# shitty_dispenser_B.net
KiCad netlist of a schematic drawn in EAGLE
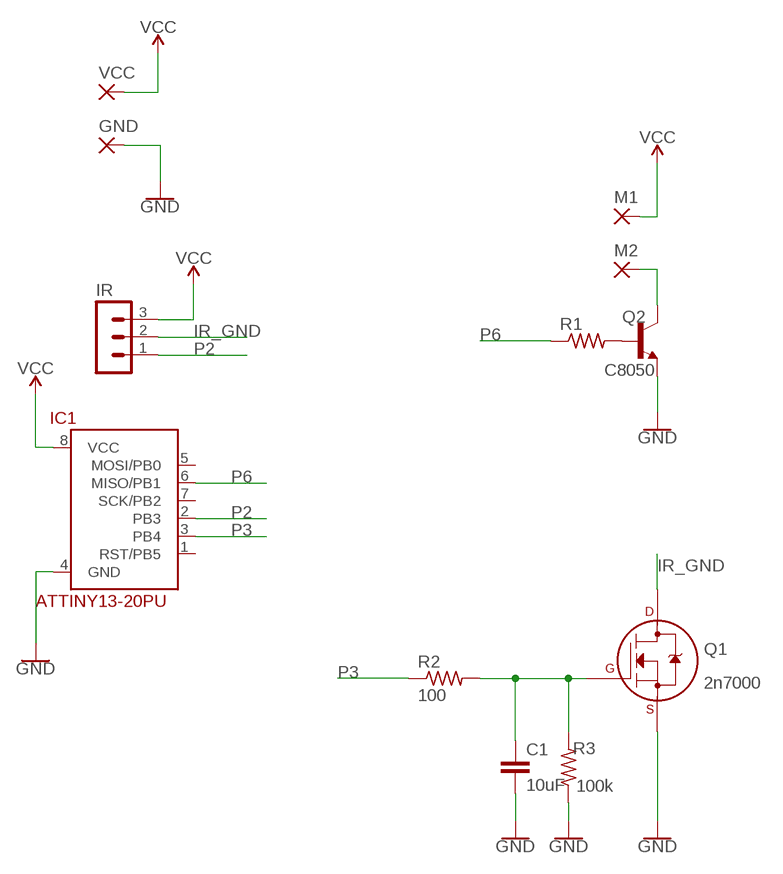
[diagram p0: schematic, sheet 1]

(export (version "E")
  (design (tool "Eeschema 10.0.6"))
  (components
    (comp (ref "C1")
      (value "10uF")
      (footprint "eagle-import:C025-025X050")
      (libsource (lib "eagle-import") (part "C-EU025-025X050"))
    )
    (comp (ref "GND")
      (value "2,54/1,0")
      (footprint "eagle-import:2,54_1,0")
      (libsource (lib "eagle-import") (part "wirepad_412_2,54/1,0"))
    )
    (comp (ref "IC1")
      (value "ATTINY13-20PU")
      (footprint "eagle-import:DIL08")
      (libsource (lib "eagle-import") (part "ATTINY13-20PU"))
    )
    (comp (ref "IR")
      (value "MA03-1")
      (footprint "eagle-import:MA03-1")
      (libsource (lib "eagle-import") (part "MA03-1"))
    )
    (comp (ref "M1")
      (value "2,54/1,0")
      (footprint "eagle-import:2,54_1,0")
      (libsource (lib "eagle-import") (part "2,54/1,0"))
    )
    (comp (ref "M2")
      (value "2,54/1,0")
      (footprint "eagle-import:2,54_1,0")
      (libsource (lib "eagle-import") (part "2,54/1,0"))
    )
    (comp (ref "Q1")
      (value "2n7000")
      (footprint "eagle-import:TO92-")
      (libsource (lib "eagle-import") (part "2N700_TO92-"))
    )
    (comp (ref "Q2")
      (value "C8050")
      (footprint "eagle-import:TO92-EBC")
      (libsource (lib "eagle-import") (part "-NPN-TO92-EBC29"))
    )
    (comp (ref "R1")
      (value "R-US_0204/7")
      (footprint "eagle-import:0204_7")
      (libsource (lib "eagle-import") (part "R-US_0204/7"))
    )
    (comp (ref "R2")
      (value "100")
      (footprint "eagle-import:0204_7")
      (libsource (lib "eagle-import") (part "R-US_0204/7"))
    )
    (comp (ref "R3")
      (value "100k")
      (footprint "eagle-import:0204_7")
      (libsource (lib "eagle-import") (part "R-US_0204/7"))
    )
    (comp (ref "VCC")
      (value "2,54/1,0")
      (footprint "eagle-import:2,54_1,0")
      (libsource (lib "eagle-import") (part "wirepad_412_2,54/1,0"))
    )
  )
  (nets
    (net (code "1") (name "/IR_GND") (class "Default")
      (node (ref "IR") (pin "2") (pinfunction "2_2") (pintype "passive"))
      (node (ref "Q1") (pin "1") (pinfunction "D_1") (pintype "bidirectional"))
    )
    (net (code "2") (name "/P2") (class "Default")
      (node (ref "IC1") (pin "2") (pinfunction "PB3_2") (pintype "bidirectional"))
      (node (ref "IR") (pin "1") (pinfunction "1_1") (pintype "passive"))
    )
    (net (code "3") (name "/P3") (class "Default")
      (node (ref "IC1") (pin "3") (pinfunction "PB4_3") (pintype "bidirectional"))
      (node (ref "R2") (pin "1") (pinfunction "1_1") (pintype "passive"))
    )
    (net (code "4") (name "/P6") (class "Default")
      (node (ref "IC1") (pin "6") (pinfunction "MISO/PB1_6") (pintype "bidirectional"))
      (node (ref "R1") (pin "1") (pinfunction "1_1") (pintype "passive"))
    )
    (net (code "5") (name "GND") (class "Default")
      (node (ref "C1") (pin "2") (pinfunction "2_2") (pintype "passive"))
      (node (ref "GND") (pin "1") (pinfunction "P_1") (pintype "passive"))
      (node (ref "IC1") (pin "4") (pinfunction "GND_4") (pintype "power_in"))
      (node (ref "Q1") (pin "3") (pinfunction "S_3") (pintype "bidirectional"))
      (node (ref "Q2") (pin "E") (pinfunction "E_E") (pintype "passive"))
      (node (ref "R3") (pin "1") (pinfunction "1_1") (pintype "passive"))
    )
    (net (code "6") (name "Net-(M2-P)") (class "Default")
      (node (ref "M2") (pin "1") (pinfunction "P_1") (pintype "passive"))
      (node (ref "Q2") (pin "C") (pinfunction "C_C") (pintype "passive"))
    )
    (net (code "7") (name "Net-(Q1-G)") (class "Default")
      (node (ref "C1") (pin "1") (pinfunction "1_1") (pintype "passive"))
      (node (ref "Q1") (pin "2") (pinfunction "G_2") (pintype "tri_state"))
      (node (ref "R2") (pin "2") (pinfunction "2_2") (pintype "passive"))
      (node (ref "R3") (pin "2") (pinfunction "2_2") (pintype "passive"))
    )
    (net (code "8") (name "Net-(Q2-PadB)") (class "Default")
      (node (ref "Q2") (pin "B") (pinfunction "B_B") (pintype "passive"))
      (node (ref "R1") (pin "2") (pinfunction "2_2") (pintype "passive"))
    )
    (net (code "9") (name "VCC") (class "Default")
      (node (ref "IC1") (pin "8") (pinfunction "VCC_8") (pintype "power_in"))
      (node (ref "IR") (pin "3") (pinfunction "3_3") (pintype "passive"))
      (node (ref "M1") (pin "1") (pinfunction "P_1") (pintype "passive"))
      (node (ref "VCC") (pin "1") (pinfunction "P_1") (pintype "passive"))
    )
    (net (code "10") (name "unconnected-(IC1-MOSI{slash}PB0-Pad5)") (class "Default")
      (node (ref "IC1") (pin "5") (pinfunction "MOSI/PB0_5") (pintype "bidirectional"))
    )
    (net (code "11") (name "unconnected-(IC1-RST{slash}PB5-Pad1)") (class "Default")
      (node (ref "IC1") (pin "1") (pinfunction "RST/PB5_1") (pintype "bidirectional"))
    )
    (net (code "12") (name "unconnected-(IC1-SCK{slash}PB2-Pad7)") (class "Default")
      (node (ref "IC1") (pin "7") (pinfunction "SCK/PB2_7") (pintype "bidirectional"))
    )
  )
)
